# FPGA_Supply.net
KiCad netlist of a schematic drawn in Altium Designer
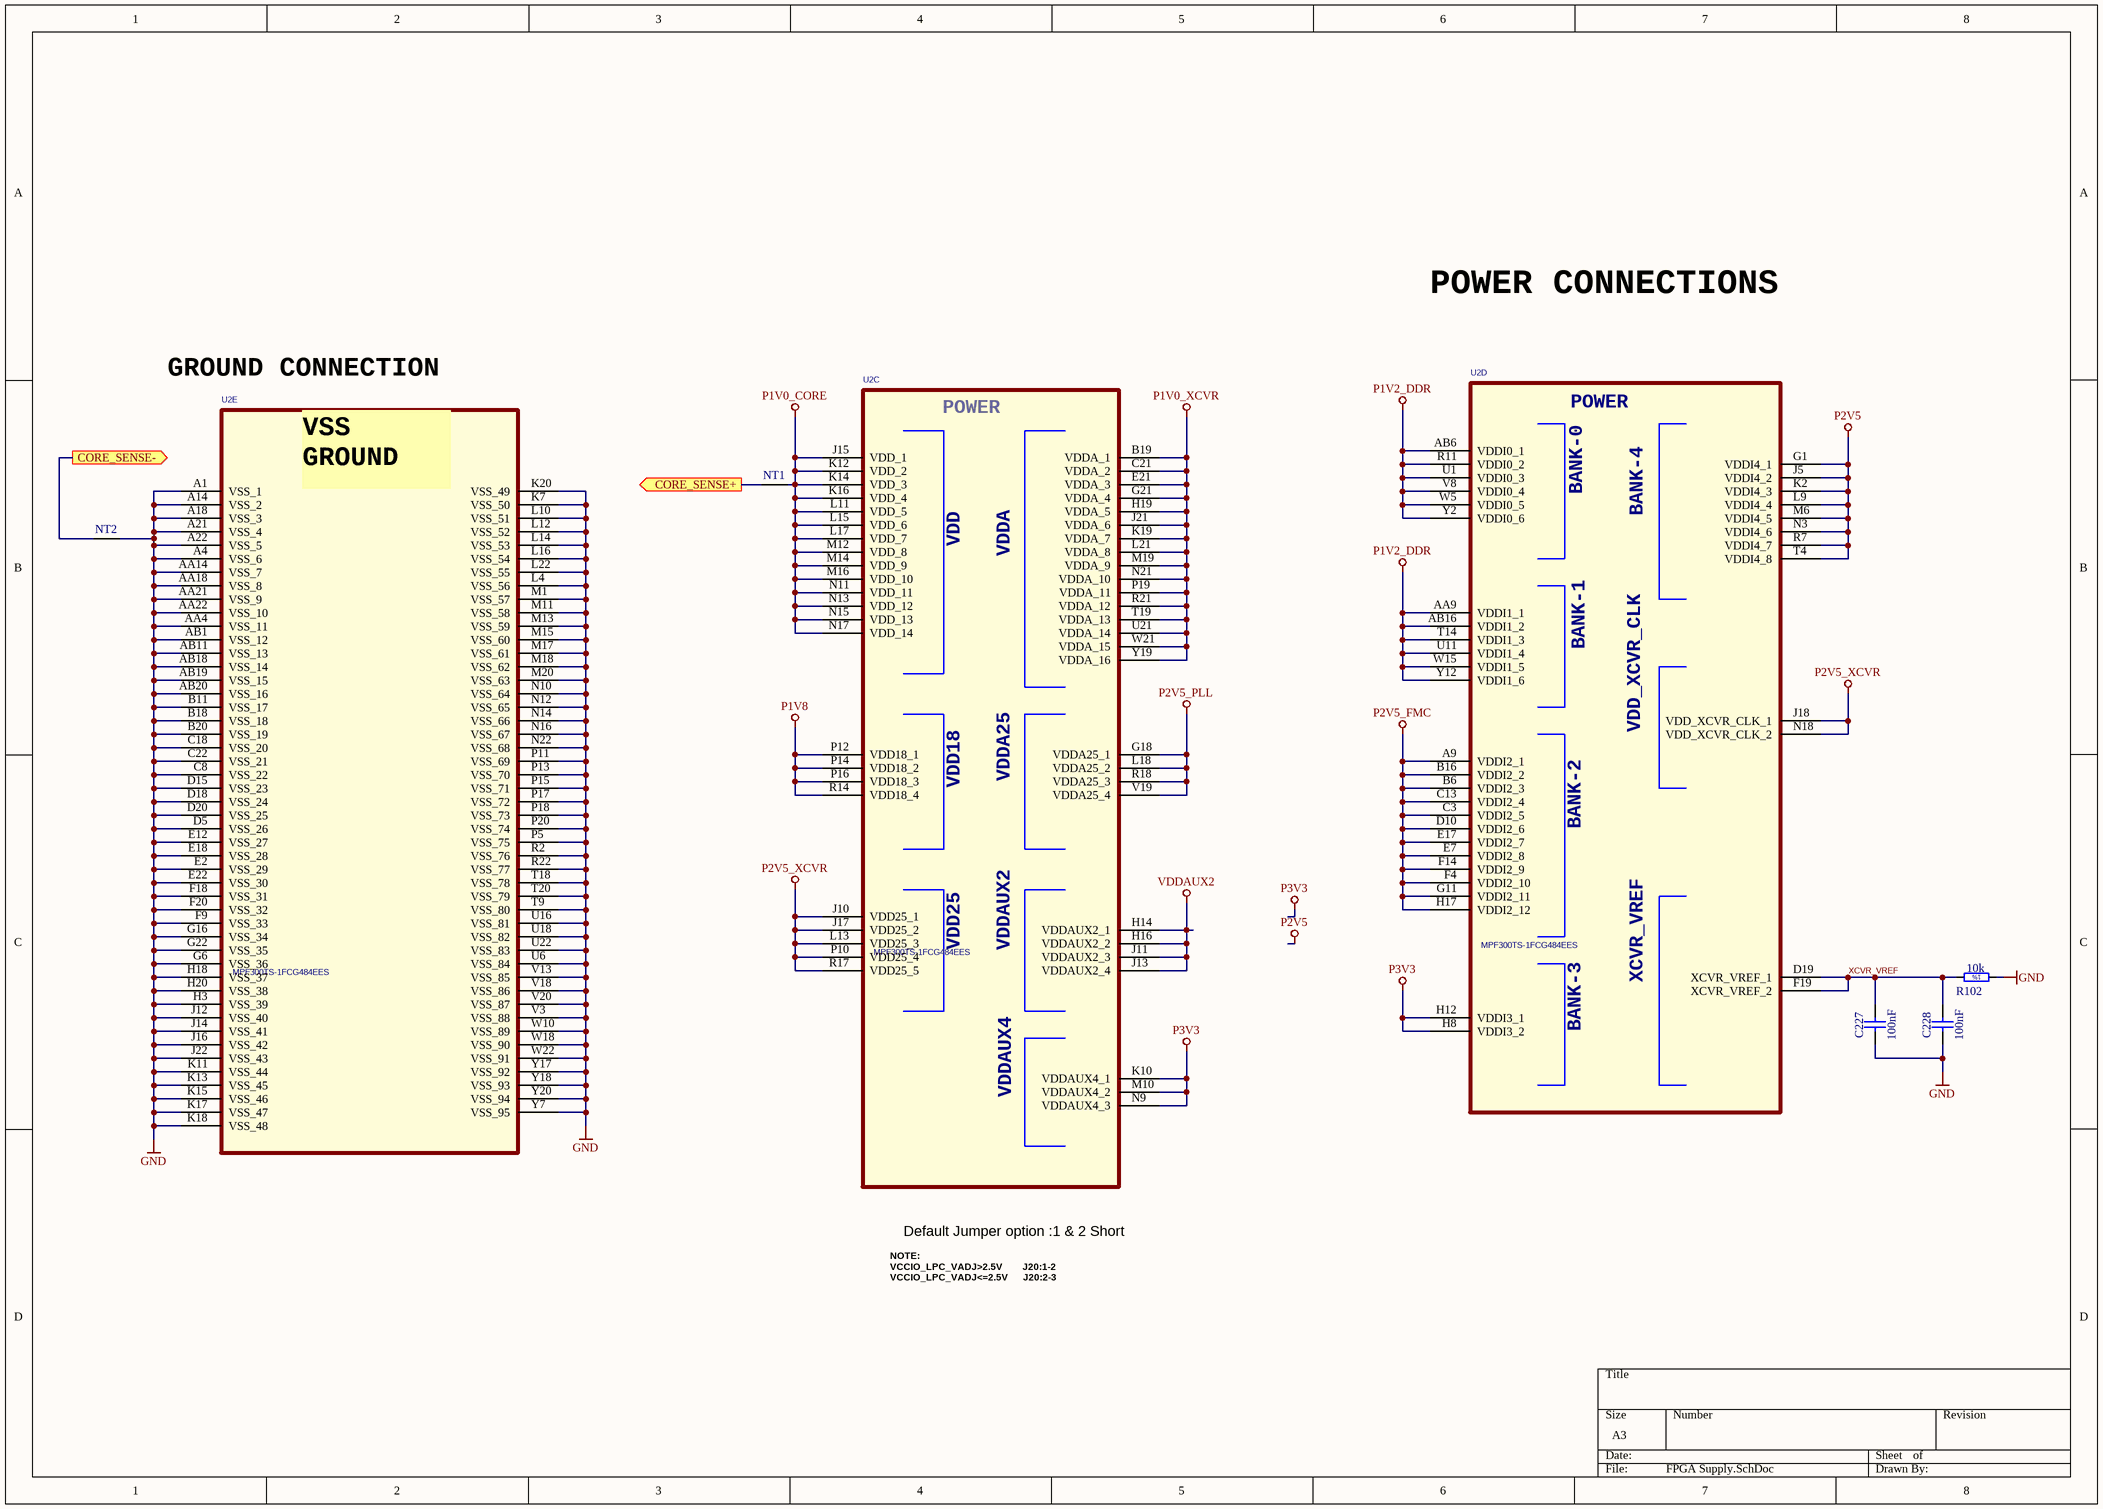
[diagram p0: FPGA Supply.SchDoc]

(export (version "E")
  (design (tool "Eeschema 10.0.6"))
  (components
    (comp (ref "C227")
      (value "100nF")
      (footprint "CAPC0603X33N")
      (description "Non-polarised capacitor")
      (fields
        (field (name "MANUFACTURER") "GENERIC")
        (field (name "PART NUMBER") "CC0201_100NF_6.3V_10%_X5R")
        (field (name "AUTHOR") "CERN DEM JLC")
      )
      (libsource (lib "Capacitors") (part "Capacitor - non polarized"))
    )
    (comp (ref "C228")
      (value "100nF")
      (footprint "CAPC0603X33N")
      (description "Non-polarised capacitor")
      (fields
        (field (name "MANUFACTURER") "GENERIC")
        (field (name "PART NUMBER") "CC0201_100NF_6.3V_10%_X5R")
        (field (name "AUTHOR") "CERN DEM JLC")
      )
      (libsource (lib "Capacitors") (part "Capacitor - non polarized"))
    )
    (comp (ref "NT1")
      (value "Net Tie")
      (footprint "Net Tie")
      (fields (field (name "AUTHOR") "CERN DEM JLC"))
      (libsource (lib "Eletro-mechanical") (part "Net Tie"))
    )
    (comp (ref "NT2")
      (value "Net Tie")
      (footprint "Net Tie")
      (fields (field (name "AUTHOR") "CERN DEM JLC"))
      (libsource (lib "Eletro-mechanical") (part "Net Tie"))
    )
    (comp (ref "R102")
      (value "10k")
      (footprint "RESC1005X40N")
      (description "Resistor - 1%")
      (fields
        (field (name "MANUFACTURER PART NUMBER") "R0402_10K_1%_0.0625W_100PPM")
        (field (name "MANUFACTURER") "GENERIC")
        (field (name "AUTHOR") "CERN DEM JLC")
      )
      (libsource (lib "Resistors") (part "Resistor - 1%"))
    )
    (comp (ref "U2")
      (value "MPF300TS-1FCG484EES")
      (footprint "BGA484C100P22X22_2300X2300X320")
      (description "FCG484,23mmX23mm,1.0mm pitch")
      (fields (field (name "MANUFACTURER") "Microsemi") (field (name "PART NUMBER") "MPF300TS-1FCG484I"))
      (libsource (lib "LIBRARY_SCH") (part "FPGA_MPF300T-FCG484"))
    )
  )
  (nets
    (net (code "1") (name "/CORE_SENSE+") (class "Default")
      (node (ref "NT1") (pin "1") (pinfunction "1_1") (pintype "bidirectional"))
    )
    (net (code "2") (name "/CORE_SENSE-") (class "Default")
      (node (ref "NT2") (pin "1") (pinfunction "1_1") (pintype "bidirectional"))
    )
    (net (code "3") (name "/XCVR_VREF") (class "Default")
      (node (ref "C227") (pin "2") (pinfunction "2_2") (pintype "passive"))
      (node (ref "C228") (pin "2") (pinfunction "2_2") (pintype "passive"))
      (node (ref "R102") (pin "2") (pinfunction "2_2") (pintype "passive"))
      (node (ref "U2") (pin "D19") (pinfunction "XCVR_VREF_1_D19") (pintype "passive"))
      (node (ref "U2") (pin "F19") (pinfunction "XCVR_VREF_2_F19") (pintype "passive"))
    )
    (net (code "4") (name "GND") (class "Default")
      (node (ref "C227") (pin "1") (pinfunction "1_1") (pintype "passive"))
      (node (ref "C228") (pin "1") (pinfunction "1_1") (pintype "passive"))
      (node (ref "NT2") (pin "2") (pinfunction "2_2") (pintype "bidirectional"))
      (node (ref "R102") (pin "1") (pinfunction "1_1") (pintype "passive"))
      (node (ref "U2") (pin "A1") (pinfunction "VSS_1_A1") (pintype "passive"))
      (node (ref "U2") (pin "A14") (pinfunction "VSS_2_A14") (pintype "passive"))
      (node (ref "U2") (pin "A18") (pinfunction "VSS_3_A18") (pintype "passive"))
      (node (ref "U2") (pin "A21") (pinfunction "VSS_4_A21") (pintype "passive"))
      (node (ref "U2") (pin "A22") (pinfunction "VSS_5_A22") (pintype "passive"))
      (node (ref "U2") (pin "A4") (pinfunction "VSS_6_A4") (pintype "passive"))
      (node (ref "U2") (pin "AA14") (pinfunction "VSS_7_AA14") (pintype "passive"))
      (node (ref "U2") (pin "AA18") (pinfunction "VSS_8_AA18") (pintype "passive"))
      (node (ref "U2") (pin "AA21") (pinfunction "VSS_9_AA21") (pintype "passive"))
      (node (ref "U2") (pin "AA22") (pinfunction "VSS_10_AA22") (pintype "passive"))
      (node (ref "U2") (pin "AA4") (pinfunction "VSS_11_AA4") (pintype "passive"))
      (node (ref "U2") (pin "AB1") (pinfunction "VSS_12_AB1") (pintype "passive"))
      (node (ref "U2") (pin "AB11") (pinfunction "VSS_13_AB11") (pintype "passive"))
      (node (ref "U2") (pin "AB18") (pinfunction "VSS_14_AB18") (pintype "passive"))
      (node (ref "U2") (pin "AB19") (pinfunction "VSS_15_AB19") (pintype "passive"))
      (node (ref "U2") (pin "AB20") (pinfunction "VSS_16_AB20") (pintype "passive"))
      (node (ref "U2") (pin "B11") (pinfunction "VSS_17_B11") (pintype "passive"))
      (node (ref "U2") (pin "B18") (pinfunction "VSS_18_B18") (pintype "passive"))
      (node (ref "U2") (pin "B20") (pinfunction "VSS_19_B20") (pintype "passive"))
      (node (ref "U2") (pin "C18") (pinfunction "VSS_20_C18") (pintype "passive"))
      (node (ref "U2") (pin "C22") (pinfunction "VSS_21_C22") (pintype "passive"))
      (node (ref "U2") (pin "C8") (pinfunction "VSS_22_C8") (pintype "passive"))
      (node (ref "U2") (pin "D15") (pinfunction "VSS_23_D15") (pintype "passive"))
      (node (ref "U2") (pin "D18") (pinfunction "VSS_24_D18") (pintype "passive"))
      (node (ref "U2") (pin "D20") (pinfunction "VSS_25_D20") (pintype "passive"))
      (node (ref "U2") (pin "D5") (pinfunction "VSS_26_D5") (pintype "passive"))
      (node (ref "U2") (pin "E12") (pinfunction "VSS_27_E12") (pintype "passive"))
      (node (ref "U2") (pin "E18") (pinfunction "VSS_28_E18") (pintype "passive"))
      (node (ref "U2") (pin "E2") (pinfunction "VSS_29_E2") (pintype "passive"))
      (node (ref "U2") (pin "E22") (pinfunction "VSS_30_E22") (pintype "passive"))
      (node (ref "U2") (pin "F18") (pinfunction "VSS_31_F18") (pintype "passive"))
      (node (ref "U2") (pin "F20") (pinfunction "VSS_32_F20") (pintype "passive"))
      (node (ref "U2") (pin "F9") (pinfunction "VSS_33_F9") (pintype "passive"))
      (node (ref "U2") (pin "G16") (pinfunction "VSS_34_G16") (pintype "passive"))
      (node (ref "U2") (pin "G22") (pinfunction "VSS_35_G22") (pintype "passive"))
      (node (ref "U2") (pin "G6") (pinfunction "VSS_36_G6") (pintype "passive"))
      (node (ref "U2") (pin "H18") (pinfunction "VSS_37_H18") (pintype "passive"))
      (node (ref "U2") (pin "H20") (pinfunction "VSS_38_H20") (pintype "passive"))
      (node (ref "U2") (pin "H3") (pinfunction "VSS_39_H3") (pintype "passive"))
      (node (ref "U2") (pin "J12") (pinfunction "VSS_40_J12") (pintype "passive"))
      (node (ref "U2") (pin "J14") (pinfunction "VSS_41_J14") (pintype "passive"))
      (node (ref "U2") (pin "J16") (pinfunction "VSS_42_J16") (pintype "passive"))
      (node (ref "U2") (pin "J22") (pinfunction "VSS_43_J22") (pintype "passive"))
      (node (ref "U2") (pin "K11") (pinfunction "VSS_44_K11") (pintype "passive"))
      (node (ref "U2") (pin "K13") (pinfunction "VSS_45_K13") (pintype "passive"))
      (node (ref "U2") (pin "K15") (pinfunction "VSS_46_K15") (pintype "passive"))
      (node (ref "U2") (pin "K17") (pinfunction "VSS_47_K17") (pintype "passive"))
      (node (ref "U2") (pin "K18") (pinfunction "VSS_48_K18") (pintype "passive"))
      (node (ref "U2") (pin "K20") (pinfunction "VSS_49_K20") (pintype "passive"))
      (node (ref "U2") (pin "K7") (pinfunction "VSS_50_K7") (pintype "passive"))
      (node (ref "U2") (pin "L10") (pinfunction "VSS_51_L10") (pintype "passive"))
      (node (ref "U2") (pin "L12") (pinfunction "VSS_52_L12") (pintype "passive"))
      (node (ref "U2") (pin "L14") (pinfunction "VSS_53_L14") (pintype "passive"))
      (node (ref "U2") (pin "L16") (pinfunction "VSS_54_L16") (pintype "passive"))
      (node (ref "U2") (pin "L22") (pinfunction "VSS_55_L22") (pintype "passive"))
      (node (ref "U2") (pin "L4") (pinfunction "VSS_56_L4") (pintype "passive"))
      (node (ref "U2") (pin "M1") (pinfunction "VSS_57_M1") (pintype "passive"))
      (node (ref "U2") (pin "M11") (pinfunction "VSS_58_M11") (pintype "passive"))
      (node (ref "U2") (pin "M13") (pinfunction "VSS_59_M13") (pintype "passive"))
      (node (ref "U2") (pin "M15") (pinfunction "VSS_60_M15") (pintype "passive"))
      (node (ref "U2") (pin "M17") (pinfunction "VSS_61_M17") (pintype "passive"))
      (node (ref "U2") (pin "M18") (pinfunction "VSS_62_M18") (pintype "passive"))
      (node (ref "U2") (pin "M20") (pinfunction "VSS_63_M20") (pintype "passive"))
      (node (ref "U2") (pin "N10") (pinfunction "VSS_64_N10") (pintype "passive"))
      (node (ref "U2") (pin "N12") (pinfunction "VSS_65_N12") (pintype "passive"))
      (node (ref "U2") (pin "N14") (pinfunction "VSS_66_N14") (pintype "passive"))
      (node (ref "U2") (pin "N16") (pinfunction "VSS_67_N16") (pintype "passive"))
      (node (ref "U2") (pin "N22") (pinfunction "VSS_68_N22") (pintype "passive"))
      (node (ref "U2") (pin "P11") (pinfunction "VSS_69_P11") (pintype "passive"))
      (node (ref "U2") (pin "P13") (pinfunction "VSS_70_P13") (pintype "passive"))
      (node (ref "U2") (pin "P15") (pinfunction "VSS_71_P15") (pintype "passive"))
      (node (ref "U2") (pin "P17") (pinfunction "VSS_72_P17") (pintype "passive"))
      (node (ref "U2") (pin "P18") (pinfunction "VSS_73_P18") (pintype "passive"))
      (node (ref "U2") (pin "P20") (pinfunction "VSS_74_P20") (pintype "passive"))
      (node (ref "U2") (pin "P5") (pinfunction "VSS_75_P5") (pintype "passive"))
      (node (ref "U2") (pin "R2") (pinfunction "VSS_76_R2") (pintype "passive"))
      (node (ref "U2") (pin "R22") (pinfunction "VSS_77_R22") (pintype "passive"))
      (node (ref "U2") (pin "T18") (pinfunction "VSS_78_T18") (pintype "passive"))
      (node (ref "U2") (pin "T20") (pinfunction "VSS_79_T20") (pintype "passive"))
      (node (ref "U2") (pin "T9") (pinfunction "VSS_80_T9") (pintype "passive"))
      (node (ref "U2") (pin "U16") (pinfunction "VSS_81_U16") (pintype "passive"))
      (node (ref "U2") (pin "U18") (pinfunction "VSS_82_U18") (pintype "passive"))
      (node (ref "U2") (pin "U22") (pinfunction "VSS_83_U22") (pintype "passive"))
      (node (ref "U2") (pin "U6") (pinfunction "VSS_84_U6") (pintype "passive"))
      (node (ref "U2") (pin "V13") (pinfunction "VSS_85_V13") (pintype "passive"))
      (node (ref "U2") (pin "V18") (pinfunction "VSS_86_V18") (pintype "passive"))
      (node (ref "U2") (pin "V20") (pinfunction "VSS_87_V20") (pintype "passive"))
      (node (ref "U2") (pin "V3") (pinfunction "VSS_88_V3") (pintype "passive"))
      (node (ref "U2") (pin "W10") (pinfunction "VSS_89_W10") (pintype "passive"))
      (node (ref "U2") (pin "W18") (pinfunction "VSS_90_W18") (pintype "passive"))
      (node (ref "U2") (pin "W22") (pinfunction "VSS_91_W22") (pintype "passive"))
      (node (ref "U2") (pin "Y17") (pinfunction "VSS_92_Y17") (pintype "passive"))
      (node (ref "U2") (pin "Y18") (pinfunction "VSS_93_Y18") (pintype "passive"))
      (node (ref "U2") (pin "Y20") (pinfunction "VSS_94_Y20") (pintype "passive"))
      (node (ref "U2") (pin "Y7") (pinfunction "VSS_95_Y7") (pintype "passive"))
    )
    (net (code "5") (name "P1V0_CORE") (class "Default")
      (node (ref "NT1") (pin "2") (pinfunction "2_2") (pintype "bidirectional"))
      (node (ref "U2") (pin "J15") (pinfunction "VDD_1_J15") (pintype "passive"))
      (node (ref "U2") (pin "K12") (pinfunction "VDD_2_K12") (pintype "passive"))
      (node (ref "U2") (pin "K14") (pinfunction "VDD_3_K14") (pintype "passive"))
      (node (ref "U2") (pin "K16") (pinfunction "VDD_4_K16") (pintype "passive"))
      (node (ref "U2") (pin "L11") (pinfunction "VDD_5_L11") (pintype "passive"))
      (node (ref "U2") (pin "L15") (pinfunction "VDD_6_L15") (pintype "passive"))
      (node (ref "U2") (pin "L17") (pinfunction "VDD_7_L17") (pintype "passive"))
      (node (ref "U2") (pin "M12") (pinfunction "VDD_8_M12") (pintype "passive"))
      (node (ref "U2") (pin "M14") (pinfunction "VDD_9_M14") (pintype "passive"))
      (node (ref "U2") (pin "M16") (pinfunction "VDD_10_M16") (pintype "passive"))
      (node (ref "U2") (pin "N11") (pinfunction "VDD_11_N11") (pintype "passive"))
      (node (ref "U2") (pin "N13") (pinfunction "VDD_12_N13") (pintype "passive"))
      (node (ref "U2") (pin "N15") (pinfunction "VDD_13_N15") (pintype "passive"))
      (node (ref "U2") (pin "N17") (pinfunction "VDD_14_N17") (pintype "passive"))
    )
    (net (code "6") (name "P1V0_XCVR") (class "Default")
      (node (ref "U2") (pin "B19") (pinfunction "VDDA_1_B19") (pintype "passive"))
      (node (ref "U2") (pin "C21") (pinfunction "VDDA_2_C21") (pintype "passive"))
      (node (ref "U2") (pin "E21") (pinfunction "VDDA_3_E21") (pintype "passive"))
      (node (ref "U2") (pin "G21") (pinfunction "VDDA_4_G21") (pintype "passive"))
      (node (ref "U2") (pin "H19") (pinfunction "VDDA_5_H19") (pintype "passive"))
      (node (ref "U2") (pin "J21") (pinfunction "VDDA_6_J21") (pintype "passive"))
      (node (ref "U2") (pin "K19") (pinfunction "VDDA_7_K19") (pintype "passive"))
      (node (ref "U2") (pin "L21") (pinfunction "VDDA_8_L21") (pintype "passive"))
      (node (ref "U2") (pin "M19") (pinfunction "VDDA_9_M19") (pintype "passive"))
      (node (ref "U2") (pin "N21") (pinfunction "VDDA_10_N21") (pintype "passive"))
      (node (ref "U2") (pin "P19") (pinfunction "VDDA_11_P19") (pintype "passive"))
      (node (ref "U2") (pin "R21") (pinfunction "VDDA_12_R21") (pintype "passive"))
      (node (ref "U2") (pin "T19") (pinfunction "VDDA_13_T19") (pintype "passive"))
      (node (ref "U2") (pin "U21") (pinfunction "VDDA_14_U21") (pintype "passive"))
      (node (ref "U2") (pin "W21") (pinfunction "VDDA_15_W21") (pintype "passive"))
      (node (ref "U2") (pin "Y19") (pinfunction "VDDA_16_Y19") (pintype "passive"))
    )
    (net (code "7") (name "P1V2_DDR") (class "Default")
      (node (ref "U2") (pin "AA9") (pinfunction "VDDI1_1_AA9") (pintype "passive"))
      (node (ref "U2") (pin "AB16") (pinfunction "VDDI1_2_AB16") (pintype "passive"))
      (node (ref "U2") (pin "AB6") (pinfunction "VDDI0_1_AB6") (pintype "passive"))
      (node (ref "U2") (pin "R11") (pinfunction "VDDI0_2_R11") (pintype "passive"))
      (node (ref "U2") (pin "T14") (pinfunction "VDDI1_3_T14") (pintype "passive"))
      (node (ref "U2") (pin "U1") (pinfunction "VDDI0_3_U1") (pintype "passive"))
      (node (ref "U2") (pin "U11") (pinfunction "VDDI1_4_U11") (pintype "passive"))
      (node (ref "U2") (pin "V8") (pinfunction "VDDI0_4_V8") (pintype "passive"))
      (node (ref "U2") (pin "W15") (pinfunction "VDDI1_5_W15") (pintype "passive"))
      (node (ref "U2") (pin "W5") (pinfunction "VDDI0_5_W5") (pintype "passive"))
      (node (ref "U2") (pin "Y12") (pinfunction "VDDI1_6_Y12") (pintype "passive"))
      (node (ref "U2") (pin "Y2") (pinfunction "VDDI0_6_Y2") (pintype "passive"))
    )
    (net (code "8") (name "P1V8") (class "Default")
      (node (ref "U2") (pin "P12") (pinfunction "VDD18_1_P12") (pintype "passive"))
      (node (ref "U2") (pin "P14") (pinfunction "VDD18_2_P14") (pintype "passive"))
      (node (ref "U2") (pin "P16") (pinfunction "VDD18_3_P16") (pintype "passive"))
      (node (ref "U2") (pin "R14") (pinfunction "VDD18_4_R14") (pintype "passive"))
    )
    (net (code "9") (name "P2V5") (class "Default")
      (node (ref "U2") (pin "G1") (pinfunction "VDDI4_1_G1") (pintype "passive"))
      (node (ref "U2") (pin "J5") (pinfunction "VDDI4_2_J5") (pintype "passive"))
      (node (ref "U2") (pin "K2") (pinfunction "VDDI4_3_K2") (pintype "passive"))
      (node (ref "U2") (pin "L9") (pinfunction "VDDI4_4_L9") (pintype "passive"))
      (node (ref "U2") (pin "M6") (pinfunction "VDDI4_5_M6") (pintype "passive"))
      (node (ref "U2") (pin "N3") (pinfunction "VDDI4_6_N3") (pintype "passive"))
      (node (ref "U2") (pin "R7") (pinfunction "VDDI4_7_R7") (pintype "passive"))
      (node (ref "U2") (pin "T4") (pinfunction "VDDI4_8_T4") (pintype "passive"))
    )
    (net (code "10") (name "P2V5_FMC") (class "Default")
      (node (ref "U2") (pin "A9") (pinfunction "VDDI2_1_A9") (pintype "passive"))
      (node (ref "U2") (pin "B16") (pinfunction "VDDI2_2_B16") (pintype "passive"))
      (node (ref "U2") (pin "B6") (pinfunction "VDDI2_3_B6") (pintype "passive"))
      (node (ref "U2") (pin "C13") (pinfunction "VDDI2_4_C13") (pintype "passive"))
      (node (ref "U2") (pin "C3") (pinfunction "VDDI2_5_C3") (pintype "passive"))
      (node (ref "U2") (pin "D10") (pinfunction "VDDI2_6_D10") (pintype "passive"))
      (node (ref "U2") (pin "E17") (pinfunction "VDDI2_7_E17") (pintype "passive"))
      (node (ref "U2") (pin "E7") (pinfunction "VDDI2_8_E7") (pintype "passive"))
      (node (ref "U2") (pin "F14") (pinfunction "VDDI2_9_F14") (pintype "passive"))
      (node (ref "U2") (pin "F4") (pinfunction "VDDI2_10_F4") (pintype "passive"))
      (node (ref "U2") (pin "G11") (pinfunction "VDDI2_11_G11") (pintype "passive"))
      (node (ref "U2") (pin "H17") (pinfunction "VDDI2_12_H17") (pintype "passive"))
    )
    (net (code "11") (name "P2V5_PLL") (class "Default")
      (node (ref "U2") (pin "G18") (pinfunction "VDDA25_1_G18") (pintype "passive"))
      (node (ref "U2") (pin "L18") (pinfunction "VDDA25_2_L18") (pintype "passive"))
      (node (ref "U2") (pin "R18") (pinfunction "VDDA25_3_R18") (pintype "passive"))
      (node (ref "U2") (pin "V19") (pinfunction "VDDA25_4_V19") (pintype "passive"))
    )
    (net (code "12") (name "P2V5_XCVR") (class "Default")
      (node (ref "U2") (pin "J10") (pinfunction "VDD25_1_J10") (pintype "passive"))
      (node (ref "U2") (pin "J17") (pinfunction "VDD25_2_J17") (pintype "passive"))
      (node (ref "U2") (pin "J18") (pinfunction "VDD_XCVR_CLK_1_J18") (pintype "passive"))
      (node (ref "U2") (pin "L13") (pinfunction "VDD25_3_L13") (pintype "passive"))
      (node (ref "U2") (pin "N18") (pinfunction "VDD_XCVR_CLK_2_N18") (pintype "passive"))
      (node (ref "U2") (pin "P10") (pinfunction "VDD25_4_P10") (pintype "passive"))
      (node (ref "U2") (pin "R17") (pinfunction "VDD25_5_R17") (pintype "passive"))
    )
    (net (code "13") (name "P3V3") (class "Default")
      (node (ref "U2") (pin "H12") (pinfunction "VDDI3_1_H12") (pintype "passive"))
      (node (ref "U2") (pin "H8") (pinfunction "VDDI3_2_H8") (pintype "passive"))
      (node (ref "U2") (pin "K10") (pinfunction "VDDAUX4_1_K10") (pintype "passive"))
      (node (ref "U2") (pin "M10") (pinfunction "VDDAUX4_2_M10") (pintype "passive"))
      (node (ref "U2") (pin "N9") (pinfunction "VDDAUX4_3_N9") (pintype "passive"))
    )
    (net (code "14") (name "VDDAUX2") (class "Default")
      (node (ref "U2") (pin "H14") (pinfunction "VDDAUX2_1_H14") (pintype "passive"))
      (node (ref "U2") (pin "H16") (pinfunction "VDDAUX2_2_H16") (pintype "passive"))
      (node (ref "U2") (pin "J11") (pinfunction "VDDAUX2_3_J11") (pintype "passive"))
      (node (ref "U2") (pin "J13") (pinfunction "VDDAUX2_4_J13") (pintype "passive"))
    )
  )
)
